# MCU.net
KiCad netlist of a schematic drawn in Altium Designer
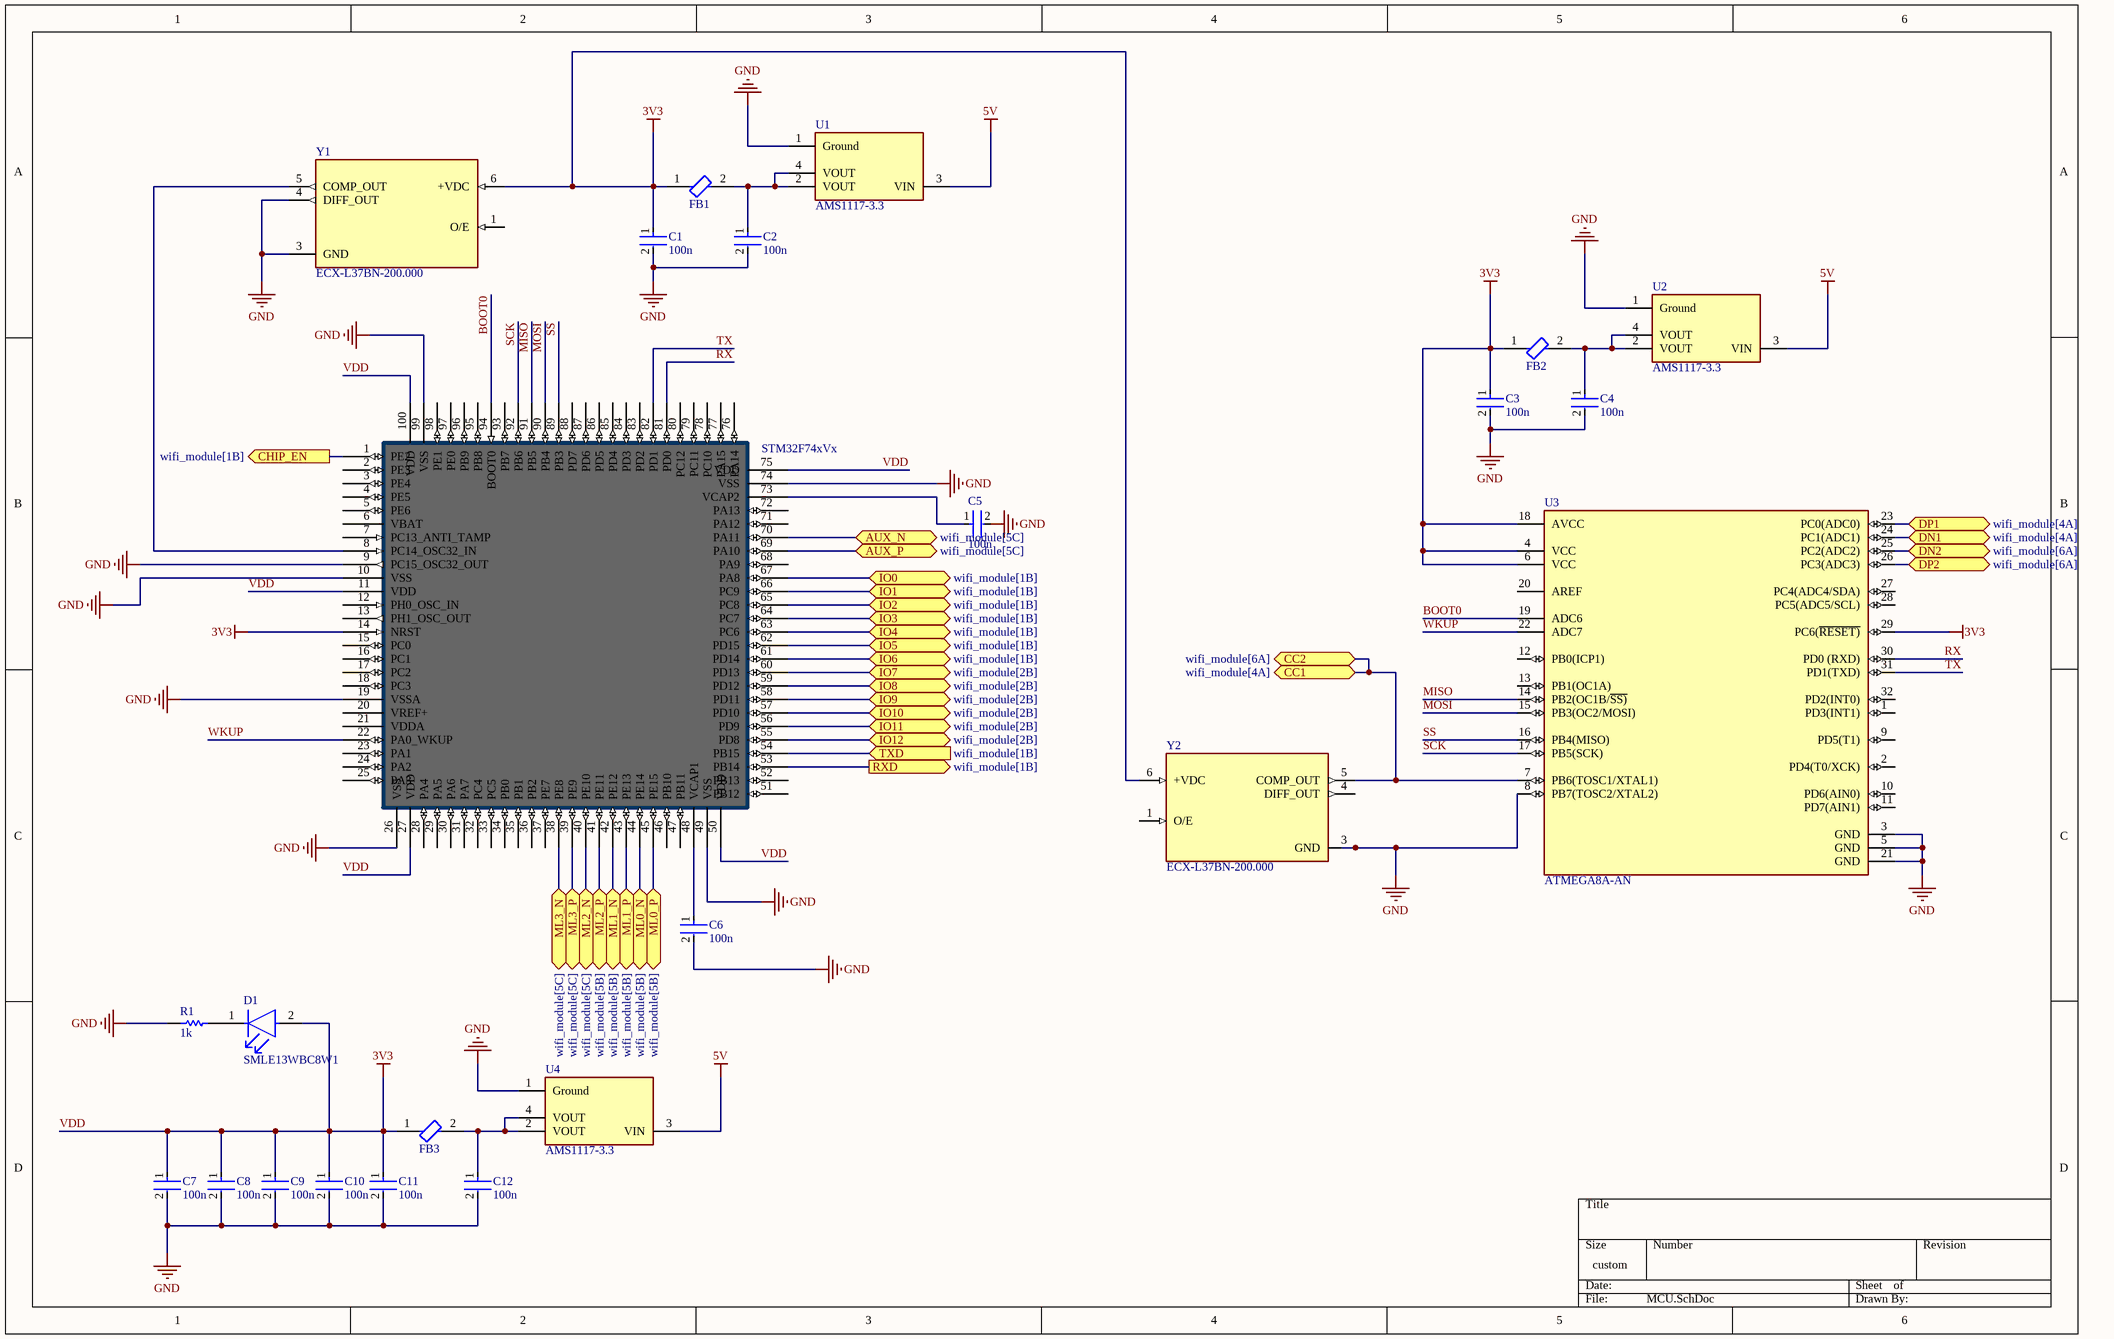
[diagram p0: MCU.SchDoc]

(export (version "E")
  (design (tool "Eeschema 10.0.6"))
  (components
    (comp (ref "C1")
      (value "100n")
      (footprint "FP-CL10-IPC_C")
      (description "Cap Ceramic 4.7uF 10V X5R ±10% Pad SMD 0603 +85°C T/R")
      (fields (field (name "TOLERANCE") "10%"))
      (libsource (lib "Altium Content Vault") (part "b4654b650e69147ec39a6b967a45e02"))
    )
    (comp (ref "C2")
      (value "100n")
      (footprint "FP-CL10-IPC_C")
      (description "Cap Ceramic 4.7uF 10V X5R ±10% Pad SMD 0603 +85°C T/R")
      (fields (field (name "TOLERANCE") "10%"))
      (libsource (lib "Altium Content Vault") (part "b4654b650e69147ec39a6b967a45e02"))
    )
    (comp (ref "C3")
      (value "100n")
      (footprint "FP-CL10-IPC_C")
      (description "Cap Ceramic 4.7uF 10V X5R ±10% Pad SMD 0603 +85°C T/R")
      (fields (field (name "TOLERANCE") "10%"))
      (libsource (lib "Altium Content Vault") (part "b4654b650e69147ec39a6b967a45e02"))
    )
    (comp (ref "C4")
      (value "100n")
      (footprint "FP-CL10-IPC_C")
      (description "Cap Ceramic 4.7uF 10V X5R ±10% Pad SMD 0603 +85°C T/R")
      (fields (field (name "TOLERANCE") "10%"))
      (libsource (lib "Altium Content Vault") (part "b4654b650e69147ec39a6b967a45e02"))
    )
    (comp (ref "C5")
      (value "100n")
      (footprint "FP-CL10-IPC_C")
      (description "Cap Ceramic 4.7uF 10V X5R ±10% Pad SMD 0603 +85°C T/R")
      (fields (field (name "TOLERANCE") "10%"))
      (libsource (lib "Altium Content Vault") (part "b4654b650e69147ec39a6b967a45e02"))
    )
    (comp (ref "C6")
      (value "100n")
      (footprint "FP-CL10-IPC_C")
      (description "Cap Ceramic 4.7uF 10V X5R ±10% Pad SMD 0603 +85°C T/R")
      (fields (field (name "TOLERANCE") "10%"))
      (libsource (lib "Altium Content Vault") (part "b4654b650e69147ec39a6b967a45e02"))
    )
    (comp (ref "C7")
      (value "100n")
      (footprint "FP-CL10-IPC_C")
      (description "Cap Ceramic 4.7uF 10V X5R ±10% Pad SMD 0603 +85°C T/R")
      (fields (field (name "TOLERANCE") "10%"))
      (libsource (lib "Altium Content Vault") (part "b4654b650e69147ec39a6b967a45e02"))
    )
    (comp (ref "C8")
      (value "100n")
      (footprint "FP-CL10-IPC_C")
      (description "Cap Ceramic 4.7uF 10V X5R ±10% Pad SMD 0603 +85°C T/R")
      (fields (field (name "TOLERANCE") "10%"))
      (libsource (lib "Altium Content Vault") (part "b4654b650e69147ec39a6b967a45e02"))
    )
    (comp (ref "C9")
      (value "100n")
      (footprint "FP-CL10-IPC_C")
      (description "Cap Ceramic 4.7uF 10V X5R ±10% Pad SMD 0603 +85°C T/R")
      (fields (field (name "TOLERANCE") "10%"))
      (libsource (lib "Altium Content Vault") (part "b4654b650e69147ec39a6b967a45e02"))
    )
    (comp (ref "C10")
      (value "100n")
      (footprint "FP-CL10-IPC_C")
      (description "Cap Ceramic 4.7uF 10V X5R ±10% Pad SMD 0603 +85°C T/R")
      (fields (field (name "TOLERANCE") "10%"))
      (libsource (lib "Altium Content Vault") (part "b4654b650e69147ec39a6b967a45e02"))
    )
    (comp (ref "C11")
      (value "100n")
      (footprint "FP-CL10-IPC_C")
      (description "Cap Ceramic 4.7uF 10V X5R ±10% Pad SMD 0603 +85°C T/R")
      (fields (field (name "TOLERANCE") "10%"))
      (libsource (lib "Altium Content Vault") (part "b4654b650e69147ec39a6b967a45e02"))
    )
    (comp (ref "C12")
      (value "100n")
      (footprint "FP-CL10-IPC_C")
      (description "Cap Ceramic 4.7uF 10V X5R ±10% Pad SMD 0603 +85°C T/R")
      (fields (field (name "TOLERANCE") "10%"))
      (libsource (lib "Altium Content Vault") (part "b4654b650e69147ec39a6b967a45e02"))
    )
    (comp (ref "D1")
      (value "SMLE13WBC8W1")
      (footprint "FP-SMLE13WBC8W1-MFG")
      (description "LED WHITE 0603 SMD")
      (fields
        (field (name "OCTOPART") "https://octopart.com/smle13wbc8w1-rohm-22224565")
        (field (name "MANUFACTURER") "Rohm")
      )
      (libsource (lib "Altium Content Vault") (part "8706943c75ba83719d021d2fdc84c58"))
    )
    (comp (ref "FB1")
      (value "BLM18KG121TN1D")
      (footprint "FP-BLM18-0_15-t0_6-d1_2-IPC_A")
      (description "FERRITE BEAD 120 OHM 0603 1LN")
      (fields (field (name "TOLERANCE") "25%"))
      (libsource (lib "Altium Content Vault") (part "5f30dd21d616792df468990f7003faa"))
    )
    (comp (ref "FB2")
      (value "BLM18KG121TN1D")
      (footprint "FP-BLM18-0_15-t0_6-d1_2-IPC_A")
      (description "FERRITE BEAD 120 OHM 0603 1LN")
      (fields (field (name "TOLERANCE") "25%"))
      (libsource (lib "Altium Content Vault") (part "5f30dd21d616792df468990f7003faa"))
    )
    (comp (ref "FB3")
      (value "BLM18KG121TN1D")
      (footprint "FP-BLM18-0_15-t0_6-d1_2-IPC_A")
      (description "FERRITE BEAD 120 OHM 0603 1LN")
      (fields (field (name "TOLERANCE") "25%"))
      (libsource (lib "Altium Content Vault") (part "5f30dd21d616792df468990f7003faa"))
    )
    (comp (ref "R1")
      (value "1k")
      (footprint "RESC2013X60X35ML10T20")
      (fields (field (name "TOLERANCE") "5%") (field (name "MANUFACTURER") "Yageo"))
      (libsource (lib "Altium Content Vault") (part "RES-2"))
    )
    (comp (ref "U0")
      (value "STM32F74xVx")
      (footprint "STMS:CQFP-STM32F74xVx")
      (description "STM32F74xVx LQFP100 pinout")
      (libsource (lib "STMs") (part "STM32F74xVx"))
    )
    (comp (ref "U1")
      (value "AMS1117-3.3")
      (footprint "FP-AMS1117-IPC_C")
      (description "LDO Voltage Regulators 1A, 3.3V")
      (fields
        (field (name "OCTOPART") "https://octopart.com/ams1117-3.3-advanced+monolithic+systems-25899300")
        (field (name "MANUFACTURER") "Advanced Monolithic Systems")
      )
      (libsource (lib "Altium Content Vault") (part "8bdbb5f8e77002000e30dd2845d0354"))
    )
    (comp (ref "U2")
      (value "AMS1117-3.3")
      (footprint "FP-AMS1117-IPC_C")
      (description "LDO Voltage Regulators 1A, 3.3V")
      (fields
        (field (name "OCTOPART") "https://octopart.com/ams1117-3.3-advanced+monolithic+systems-25899300")
        (field (name "MANUFACTURER") "Advanced Monolithic Systems")
      )
      (libsource (lib "Altium Content Vault") (part "8bdbb5f8e77002000e30dd2845d0354"))
    )
    (comp (ref "U3")
      (value "ATMEGA8A-AN")
      (footprint "FP-C04-074-PT-MFG")
      (description "ATMEGA8A-AN RISC Microcontroller, 8-Bit, FLASH, 16MHz, CMOS, PQFP32")
      (libsource (lib "Altium Content Vault") (part "c0b57bf7e3282e7022ba109d8523e59"))
    )
    (comp (ref "U4")
      (value "AMS1117-3.3")
      (footprint "FP-AMS1117-IPC_C")
      (description "LDO Voltage Regulators 1A, 3.3V")
      (fields
        (field (name "OCTOPART") "https://octopart.com/ams1117-3.3-advanced+monolithic+systems-25899300")
        (field (name "MANUFACTURER") "Advanced Monolithic Systems")
      )
      (libsource (lib "Altium Content Vault") (part "8bdbb5f8e77002000e30dd2845d0354"))
    )
    (comp (ref "Y1")
      (value "ECX-L37BN-200.000")
      (footprint "OSC_ECX-L37BN-200.000")
      (description "200 MHz XO (Standard) LVDS Oscillator 3.3V Enable/Disable 6-SMD, No Lead")
      (fields (field (name "MF") "ECS Inc."))
      (libsource (lib "ECX-L37BN-200.000") (part "ECX-L37BN-200.000"))
    )
    (comp (ref "Y2")
      (value "ECX-L37BN-200.000")
      (footprint "OSC_ECX-L37BN-200.000")
      (description "200 MHz XO (Standard) LVDS Oscillator 3.3V Enable/Disable 6-SMD, No Lead")
      (fields (field (name "MF") "ECS Inc."))
      (libsource (lib "") (part "ECX-L37BN-200.000_1"))
    )
  )
  (nets
    (net (code "1") (name "/AUX_N") (class "Default")
      (node (ref "U0") (pin "70") (pinfunction "PA11_70") (pintype "bidirectional"))
    )
    (net (code "2") (name "/AUX_P") (class "Default")
      (node (ref "U0") (pin "69") (pinfunction "PA10_69") (pintype "bidirectional"))
    )
    (net (code "3") (name "/BOOT0") (class "Default")
      (node (ref "U0") (pin "94") (pinfunction "BOOT0_94") (pintype "input"))
      (node (ref "U3") (pin "19") (pinfunction "ADC6_19") (pintype "passive"))
    )
    (net (code "4") (name "/CC1") (class "Default")
      (node (ref "U3") (pin "7") (pinfunction "PB6(TOSC1/XTAL1)_7") (pintype "bidirectional"))
      (node (ref "Y2") (pin "5") (pinfunction "COMP_OUT_5") (pintype "output"))
    )
    (net (code "5") (name "/CHIP_EN") (class "Default")
      (node (ref "U0") (pin "1") (pinfunction "PE2_1") (pintype "bidirectional"))
    )
    (net (code "6") (name "/DN1") (class "Default")
      (node (ref "U3") (pin "24") (pinfunction "PC1(ADC1)_24") (pintype "bidirectional"))
    )
    (net (code "7") (name "/DN2") (class "Default")
      (node (ref "U3") (pin "25") (pinfunction "PC2(ADC2)_25") (pintype "bidirectional"))
    )
    (net (code "8") (name "/DP1") (class "Default")
      (node (ref "U3") (pin "23") (pinfunction "PC0(ADC0)_23") (pintype "bidirectional"))
    )
    (net (code "9") (name "/DP2") (class "Default")
      (node (ref "U3") (pin "26") (pinfunction "PC3(ADC3)_26") (pintype "bidirectional"))
    )
    (net (code "10") (name "/IO0") (class "Default")
      (node (ref "U0") (pin "67") (pinfunction "PA8_67") (pintype "bidirectional"))
    )
    (net (code "11") (name "/IO1") (class "Default")
      (node (ref "U0") (pin "66") (pinfunction "PC9_66") (pintype "bidirectional"))
    )
    (net (code "12") (name "/IO2") (class "Default")
      (node (ref "U0") (pin "65") (pinfunction "PC8_65") (pintype "bidirectional"))
    )
    (net (code "13") (name "/IO3") (class "Default")
      (node (ref "U0") (pin "64") (pinfunction "PC7_64") (pintype "bidirectional"))
    )
    (net (code "14") (name "/IO4") (class "Default")
      (node (ref "U0") (pin "63") (pinfunction "PC6_63") (pintype "bidirectional"))
    )
    (net (code "15") (name "/IO5") (class "Default")
      (node (ref "U0") (pin "62") (pinfunction "PD15_62") (pintype "bidirectional"))
    )
    (net (code "16") (name "/IO6") (class "Default")
      (node (ref "U0") (pin "61") (pinfunction "PD14_61") (pintype "bidirectional"))
    )
    (net (code "17") (name "/IO7") (class "Default")
      (node (ref "U0") (pin "60") (pinfunction "PD13_60") (pintype "bidirectional"))
    )
    (net (code "18") (name "/IO8") (class "Default")
      (node (ref "U0") (pin "59") (pinfunction "PD12_59") (pintype "bidirectional"))
    )
    (net (code "19") (name "/IO9") (class "Default")
      (node (ref "U0") (pin "58") (pinfunction "PD11_58") (pintype "bidirectional"))
    )
    (net (code "20") (name "/IO10") (class "Default")
      (node (ref "U0") (pin "57") (pinfunction "PD10_57") (pintype "bidirectional"))
    )
    (net (code "21") (name "/IO11") (class "Default")
      (node (ref "U0") (pin "56") (pinfunction "PD9_56") (pintype "bidirectional"))
    )
    (net (code "22") (name "/IO12") (class "Default")
      (node (ref "U0") (pin "55") (pinfunction "PD8_55") (pintype "bidirectional"))
    )
    (net (code "23") (name "/MISO") (class "Default")
      (node (ref "U0") (pin "91") (pinfunction "PB5_91") (pintype "bidirectional"))
      (node (ref "U3") (pin "14") (pinfunction "PB2(OC1B/~{SS)}_14") (pintype "bidirectional"))
    )
    (net (code "24") (name "/ML0_N") (class "Default")
      (node (ref "U0") (pin "44") (pinfunction "PE14_44") (pintype "bidirectional"))
    )
    (net (code "25") (name "/ML0_P") (class "Default")
      (node (ref "U0") (pin "45") (pinfunction "PE15_45") (pintype "bidirectional"))
    )
    (net (code "26") (name "/ML1_N") (class "Default")
      (node (ref "U0") (pin "42") (pinfunction "PE12_42") (pintype "bidirectional"))
    )
    (net (code "27") (name "/ML1_P") (class "Default")
      (node (ref "U0") (pin "43") (pinfunction "PE13_43") (pintype "bidirectional"))
    )
    (net (code "28") (name "/ML2_N") (class "Default")
      (node (ref "U0") (pin "40") (pinfunction "PE10_40") (pintype "bidirectional"))
    )
    (net (code "29") (name "/ML2_P") (class "Default")
      (node (ref "U0") (pin "41") (pinfunction "PE11_41") (pintype "bidirectional"))
    )
    (net (code "30") (name "/ML3_N") (class "Default")
      (node (ref "U0") (pin "38") (pinfunction "PE8_38") (pintype "bidirectional"))
    )
    (net (code "31") (name "/ML3_P") (class "Default")
      (node (ref "U0") (pin "39") (pinfunction "PE9_39") (pintype "bidirectional"))
    )
    (net (code "32") (name "/MOSI") (class "Default")
      (node (ref "U0") (pin "90") (pinfunction "PB4_90") (pintype "bidirectional"))
      (node (ref "U3") (pin "15") (pinfunction "PB3(OC2/MOSI)_15") (pintype "bidirectional"))
    )
    (net (code "33") (name "/RX") (class "Default")
      (node (ref "U0") (pin "81") (pinfunction "PD0_81") (pintype "bidirectional"))
      (node (ref "U3") (pin "30") (pinfunction "PD0_(RXD)_30") (pintype "bidirectional"))
    )
    (net (code "34") (name "/RXD") (class "Default")
      (node (ref "U0") (pin "53") (pinfunction "PB14_53") (pintype "bidirectional"))
    )
    (net (code "35") (name "/SCK") (class "Default")
      (node (ref "U0") (pin "92") (pinfunction "PB6_92") (pintype "bidirectional"))
      (node (ref "U3") (pin "17") (pinfunction "PB5(SCK)_17") (pintype "bidirectional"))
    )
    (net (code "36") (name "/SS") (class "Default")
      (node (ref "U0") (pin "89") (pinfunction "PB3_89") (pintype "bidirectional"))
      (node (ref "U3") (pin "16") (pinfunction "PB4(MISO)_16") (pintype "bidirectional"))
    )
    (net (code "37") (name "/TX") (class "Default")
      (node (ref "U0") (pin "82") (pinfunction "PD1_82") (pintype "bidirectional"))
      (node (ref "U3") (pin "31") (pinfunction "PD1(TXD)_31") (pintype "bidirectional"))
    )
    (net (code "38") (name "/TXD") (class "Default")
      (node (ref "U0") (pin "54") (pinfunction "PB15_54") (pintype "bidirectional"))
    )
    (net (code "39") (name "/WKUP") (class "Default")
      (node (ref "U0") (pin "22") (pinfunction "PA0_WKUP_22") (pintype "bidirectional"))
      (node (ref "U3") (pin "22") (pinfunction "ADC7_22") (pintype "passive"))
    )
    (net (code "40") (name "3V3") (class "Default")
      (node (ref "C1") (pin "1") (pinfunction "1_1") (pintype "passive"))
      (node (ref "C10") (pin "1") (pinfunction "1_1") (pintype "passive"))
      (node (ref "C11") (pin "1") (pinfunction "1_1") (pintype "passive"))
      (node (ref "C3") (pin "1") (pinfunction "1_1") (pintype "passive"))
      (node (ref "C7") (pin "1") (pinfunction "1_1") (pintype "passive"))
      (node (ref "C8") (pin "1") (pinfunction "1_1") (pintype "passive"))
      (node (ref "C9") (pin "1") (pinfunction "1_1") (pintype "passive"))
      (node (ref "D1") (pin "2") (pinfunction "A_2") (pintype "passive"))
      (node (ref "FB1") (pin "1") (pinfunction "1_1") (pintype "passive"))
      (node (ref "FB2") (pin "1") (pinfunction "1_1") (pintype "passive"))
      (node (ref "FB3") (pin "1") (pinfunction "1_1") (pintype "passive"))
      (node (ref "U0") (pin "100") (pinfunction "VDD_100") (pintype "power_in"))
      (node (ref "U0") (pin "11") (pinfunction "VDD_11") (pintype "power_in"))
      (node (ref "U0") (pin "14") (pinfunction "NRST_14") (pintype "input"))
      (node (ref "U0") (pin "27") (pinfunction "VDD_27") (pintype "power_in"))
      (node (ref "U0") (pin "50") (pinfunction "VDD_50") (pintype "power_in"))
      (node (ref "U0") (pin "75") (pinfunction "VDD_75") (pintype "power_in"))
      (node (ref "U3") (pin "18") (pinfunction "AVCC_18") (pintype "power_in"))
      (node (ref "U3") (pin "29") (pinfunction "PC6(~{RESET)}_29") (pintype "bidirectional"))
      (node (ref "U3") (pin "4") (pinfunction "VCC_4") (pintype "power_in"))
      (node (ref "U3") (pin "6") (pinfunction "VCC_6") (pintype "power_in"))
      (node (ref "Y1") (pin "6") (pinfunction "+VDC_6") (pintype "input"))
      (node (ref "Y2") (pin "6") (pinfunction "+VDC_6") (pintype "input"))
    )
    (net (code "41") (name "5V") (class "Default")
      (node (ref "U1") (pin "3") (pinfunction "VIN_3") (pintype "power_in"))
      (node (ref "U2") (pin "3") (pinfunction "VIN_3") (pintype "power_in"))
      (node (ref "U4") (pin "3") (pinfunction "VIN_3") (pintype "power_in"))
    )
    (net (code "42") (name "GND") (class "Default")
      (node (ref "C1") (pin "2") (pinfunction "2_2") (pintype "passive"))
      (node (ref "C10") (pin "2") (pinfunction "2_2") (pintype "passive"))
      (node (ref "C11") (pin "2") (pinfunction "2_2") (pintype "passive"))
      (node (ref "C12") (pin "2") (pinfunction "2_2") (pintype "passive"))
      (node (ref "C2") (pin "2") (pinfunction "2_2") (pintype "passive"))
      (node (ref "C3") (pin "2") (pinfunction "2_2") (pintype "passive"))
      (node (ref "C4") (pin "2") (pinfunction "2_2") (pintype "passive"))
      (node (ref "C5") (pin "2") (pinfunction "2_2") (pintype "passive"))
      (node (ref "C6") (pin "2") (pinfunction "2_2") (pintype "passive"))
      (node (ref "C7") (pin "2") (pinfunction "2_2") (pintype "passive"))
      (node (ref "C8") (pin "2") (pinfunction "2_2") (pintype "passive"))
      (node (ref "C9") (pin "2") (pinfunction "2_2") (pintype "passive"))
      (node (ref "R1") (pin "1") (pinfunction "1_1") (pintype "passive"))
      (node (ref "U0") (pin "10") (pinfunction "VSS_10") (pintype "power_in"))
      (node (ref "U0") (pin "19") (pinfunction "VSSA_19") (pintype "power_in"))
      (node (ref "U0") (pin "26") (pinfunction "VSS_26") (pintype "power_in"))
      (node (ref "U0") (pin "49") (pinfunction "VSS_49") (pintype "power_in"))
      (node (ref "U0") (pin "74") (pinfunction "VSS_74") (pintype "power_in"))
      (node (ref "U0") (pin "9") (pinfunction "PC15_OSC32_OUT_9") (pintype "output"))
      (node (ref "U0") (pin "99") (pinfunction "VSS_99") (pintype "power_in"))
      (node (ref "U1") (pin "1") (pinfunction "Ground_1") (pintype "power_in"))
      (node (ref "U2") (pin "1") (pinfunction "Ground_1") (pintype "power_in"))
      (node (ref "U3") (pin "21") (pinfunction "GND_21") (pintype "power_in"))
      (node (ref "U3") (pin "3") (pinfunction "GND_3") (pintype "power_in"))
      (node (ref "U3") (pin "5") (pinfunction "GND_5") (pintype "power_in"))
      (node (ref "U3") (pin "8") (pinfunction "PB7(TOSC2/XTAL2)_8") (pintype "bidirectional"))
      (node (ref "U4") (pin "1") (pinfunction "Ground_1") (pintype "power_in"))
      (node (ref "Y1") (pin "3") (pinfunction "GND_3") (pintype "power_in"))
      (node (ref "Y1") (pin "4") (pinfunction "DIFF_OUT_4") (pintype "output"))
      (node (ref "Y2") (pin "3") (pinfunction "GND_3") (pintype "power_in"))
    )
    (net (code "43") (name "Net-(C2-Pad1)") (class "Default")
      (node (ref "C2") (pin "1") (pinfunction "1_1") (pintype "passive"))
      (node (ref "FB1") (pin "2") (pinfunction "2_2") (pintype "passive"))
      (node (ref "U1") (pin "2") (pinfunction "VOUT_2") (pintype "passive"))
      (node (ref "U1") (pin "4") (pinfunction "VOUT_4") (pintype "passive"))
    )
    (net (code "44") (name "Net-(C4-Pad1)") (class "Default")
      (node (ref "C4") (pin "1") (pinfunction "1_1") (pintype "passive"))
      (node (ref "FB2") (pin "2") (pinfunction "2_2") (pintype "passive"))
      (node (ref "U2") (pin "2") (pinfunction "VOUT_2") (pintype "passive"))
      (node (ref "U2") (pin "4") (pinfunction "VOUT_4") (pintype "passive"))
    )
    (net (code "45") (name "Net-(C12-Pad1)") (class "Default")
      (node (ref "C12") (pin "1") (pinfunction "1_1") (pintype "passive"))
      (node (ref "FB3") (pin "2") (pinfunction "2_2") (pintype "passive"))
      (node (ref "U4") (pin "2") (pinfunction "VOUT_2") (pintype "passive"))
      (node (ref "U4") (pin "4") (pinfunction "VOUT_4") (pintype "passive"))
    )
    (net (code "46") (name "Net-(D1-C)") (class "Default")
      (node (ref "D1") (pin "1") (pinfunction "C_1") (pintype "passive"))
      (node (ref "R1") (pin "2") (pinfunction "2_2") (pintype "passive"))
    )
    (net (code "47") (name "Net-(U0-PC14_OSC32_IN)") (class "Default")
      (node (ref "U0") (pin "8") (pinfunction "PC14_OSC32_IN_8") (pintype "input"))
      (node (ref "Y1") (pin "5") (pinfunction "COMP_OUT_5") (pintype "output"))
    )
    (net (code "48") (name "Net-(U0-VCAP1)") (class "Default")
      (node (ref "C6") (pin "1") (pinfunction "1_1") (pintype "passive"))
      (node (ref "U0") (pin "48") (pinfunction "VCAP1_48") (pintype "power_in"))
    )
    (net (code "49") (name "Net-(U0-VCAP2)") (class "Default")
      (node (ref "C5") (pin "1") (pinfunction "1_1") (pintype "passive"))
      (node (ref "U0") (pin "73") (pinfunction "VCAP2_73") (pintype "power_in"))
    )
    (net (code "50") (name "unconnected-(U0-PA1-Pad23)") (class "Default")
      (node (ref "U0") (pin "23") (pinfunction "PA1_23") (pintype "bidirectional"))
    )
    (net (code "51") (name "unconnected-(U0-PA2-Pad24)") (class "Default")
      (node (ref "U0") (pin "24") (pinfunction "PA2_24") (pintype "bidirectional"))
    )
    (net (code "52") (name "unconnected-(U0-PA3-Pad25)") (class "Default")
      (node (ref "U0") (pin "25") (pinfunction "PA3_25") (pintype "bidirectional"))
    )
    (net (code "53") (name "unconnected-(U0-PA4-Pad28)") (class "Default")
      (node (ref "U0") (pin "28") (pinfunction "PA4_28") (pintype "bidirectional"))
    )
    (net (code "54") (name "unconnected-(U0-PA5-Pad29)") (class "Default")
      (node (ref "U0") (pin "29") (pinfunction "PA5_29") (pintype "bidirectional"))
    )
    (net (code "55") (name "unconnected-(U0-PA6-Pad30)") (class "Default")
      (node (ref "U0") (pin "30") (pinfunction "PA6_30") (pintype "bidirectional"))
    )
    (net (code "56") (name "unconnected-(U0-PA7-Pad31)") (class "Default")
      (node (ref "U0") (pin "31") (pinfunction "PA7_31") (pintype "bidirectional"))
    )
    (net (code "57") (name "unconnected-(U0-PA9-Pad68)") (class "Default")
      (node (ref "U0") (pin "68") (pinfunction "PA9_68") (pintype "bidirectional"))
    )
    (net (code "58") (name "unconnected-(U0-PA12-Pad71)") (class "Default")
      (node (ref "U0") (pin "71") (pinfunction "PA12_71") (pintype "bidirectional"))
    )
    (net (code "59") (name "unconnected-(U0-PA13-Pad72)") (class "Default")
      (node (ref "U0") (pin "72") (pinfunction "PA13_72") (pintype "bidirectional"))
    )
    (net (code "60") (name "unconnected-(U0-PA14-Pad76)") (class "Default")
      (node (ref "U0") (pin "76") (pinfunction "PA14_76") (pintype "bidirectional"))
    )
    (net (code "61") (name "unconnected-(U0-PA15-Pad77)") (class "Default")
      (node (ref "U0") (pin "77") (pinfunction "PA15_77") (pintype "bidirectional"))
    )
    (net (code "62") (name "unconnected-(U0-PB0-Pad34)") (class "Default")
      (node (ref "U0") (pin "34") (pinfunction "PB0_34") (pintype "bidirectional"))
    )
    (net (code "63") (name "unconnected-(U0-PB1-Pad35)") (class "Default")
      (node (ref "U0") (pin "35") (pinfunction "PB1_35") (pintype "bidirectional"))
    )
    (net (code "64") (name "unconnected-(U0-PB2-Pad36)") (class "Default")
      (node (ref "U0") (pin "36") (pinfunction "PB2_36") (pintype "bidirectional"))
    )
    (net (code "65") (name "unconnected-(U0-PB7-Pad93)") (class "Default")
      (node (ref "U0") (pin "93") (pinfunction "PB7_93") (pintype "bidirectional"))
    )
    (net (code "66") (name "unconnected-(U0-PB8-Pad95)") (class "Default")
      (node (ref "U0") (pin "95") (pinfunction "PB8_95") (pintype "bidirectional"))
    )
    (net (code "67") (name "unconnected-(U0-PB9-Pad96)") (class "Default")
      (node (ref "U0") (pin "96") (pinfunction "PB9_96") (pintype "bidirectional"))
    )
    (net (code "68") (name "unconnected-(U0-PB10-Pad46)") (class "Default")
      (node (ref "U0") (pin "46") (pinfunction "PB10_46") (pintype "bidirectional"))
    )
    (net (code "69") (name "unconnected-(U0-PB11-Pad47)") (class "Default")
      (node (ref "U0") (pin "47") (pinfunction "PB11_47") (pintype "bidirectional"))
    )
    (net (code "70") (name "unconnected-(U0-PB12-Pad51)") (class "Default")
      (node (ref "U0") (pin "51") (pinfunction "PB12_51") (pintype "bidirectional"))
    )
    (net (code "71") (name "unconnected-(U0-PB13-Pad52)") (class "Default")
      (node (ref "U0") (pin "52") (pinfunction "PB13_52") (pintype "bidirectional"))
    )
    (net (code "72") (name "unconnected-(U0-PC0-Pad15)") (class "Default")
      (node (ref "U0") (pin "15") (pinfunction "PC0_15") (pintype "bidirectional"))
    )
    (net (code "73") (name "unconnected-(U0-PC1-Pad16)") (class "Default")
      (node (ref "U0") (pin "16") (pinfunction "PC1_16") (pintype "bidirectional"))
    )
    (net (code "74") (name "unconnected-(U0-PC2-Pad17)") (class "Default")
      (node (ref "U0") (pin "17") (pinfunction "PC2_17") (pintype "bidirectional"))
    )
    (net (code "75") (name "unconnected-(U0-PC3-Pad18)") (class "Default")
      (node (ref "U0") (pin "18") (pinfunction "PC3_18") (pintype "bidirectional"))
    )
    (net (code "76") (name "unconnected-(U0-PC4-Pad32)") (class "Default")
      (node (ref "U0") (pin "32") (pinfunction "PC4_32") (pintype "bidirectional"))
    )
    (net (code "77") (name "unconnected-(U0-PC5-Pad33)") (class "Default")
      (node (ref "U0") (pin "33") (pinfunction "PC5_33") (pintype "bidirectional"))
    )
    (net (code "78") (name "unconnected-(U0-PC10-Pad78)") (class "Default")
      (node (ref "U0") (pin "78") (pinfunction "PC10_78") (pintype "bidirectional"))
    )
    (net (code "79") (name "unconnected-(U0-PC11-Pad79)") (class "Default")
      (node (ref "U0") (pin "79") (pinfunction "PC11_79") (pintype "bidirectional"))
    )
    (net (code "80") (name "unconnected-(U0-PC12-Pad80)") (class "Default")
      (node (ref "U0") (pin "80") (pinfunction "PC12_80") (pintype "bidirectional"))
    )
    (net (code "81") (name "unconnected-(U0-PC13_ANTI_TAMP-Pad7)") (class "Default")
      (node (ref "U0") (pin "7") (pinfunction "PC13_ANTI_TAMP_7") (pintype "input"))
    )
    (net (code "82") (name "unconnected-(U0-PD2-Pad83)") (class "Default")
      (node (ref "U0") (pin "83") (pinfunction "PD2_83") (pintype "bidirectional"))
    )
    (net (code "83") (name "unconnected-(U0-PD3-Pad84)") (class "Default")
      (node (ref "U0") (pin "84") (pinfunction "PD3_84") (pintype "bidirectional"))
    )
    (net (code "84") (name "unconnected-(U0-PD4-Pad85)") (class "Default")
      (node (ref "U0") (pin "85") (pinfunction "PD4_85") (pintype "bidirectional"))
    )
    (net (code "85") (name "unconnected-(U0-PD5-Pad86)") (class "Default")
      (node (ref "U0") (pin "86") (pinfunction "PD5_86") (pintype "bidirectional"))
    )
    (net (code "86") (name "unconnected-(U0-PD6-Pad87)") (class "Default")
      (node (ref "U0") (pin "87") (pinfunction "PD6_87") (pintype "bidirectional"))
    )
    (net (code "87") (name "unconnected-(U0-PD7-Pad88)") (class "Default")
      (node (ref "U0") (pin "88") (pinfunction "PD7_88") (pintype "bidirectional"))
    )
    (net (code "88") (name "unconnected-(U0-PE0-Pad97)") (class "Default")
      (node (ref "U0") (pin "97") (pinfunction "PE0_97") (pintype "bidirectional"))
    )
    (net (code "89") (name "unconnected-(U0-PE1-Pad98)") (class "Default")
      (node (ref "U0") (pin "98") (pinfunction "PE1_98") (pintype "bidirectional"))
    )
    (net (code "90") (name "unconnected-(U0-PE3-Pad2)") (class "Default")
      (node (ref "U0") (pin "2") (pinfunction "PE3_2") (pintype "bidirectional"))
    )
    (net (code "91") (name "unconnected-(U0-PE4-Pad3)") (class "Default")
      (node (ref "U0") (pin "3") (pinfunction "PE4_3") (pintype "bidirectional"))
    )
    (net (code "92") (name "unconnected-(U0-PE5-Pad4)") (class "Default")
      (node (ref "U0") (pin "4") (pinfunction "PE5_4") (pintype "bidirectional"))
    )
    (net (code "93") (name "unconnected-(U0-PE6-Pad5)") (class "Default")
      (node (ref "U0") (pin "5") (pinfunction "PE6_5") (pintype "bidirectional"))
    )
    (net (code "94") (name "unconnected-(U0-PE7-Pad37)") (class "Default")
      (node (ref "U0") (pin "37") (pinfunction "PE7_37") (pintype "bidirectional"))
    )
    (net (code "95") (name "unconnected-(U0-PH0_OSC_IN-Pad12)") (class "Default")
      (node (ref "U0") (pin "12") (pinfunction "PH0_OSC_IN_12") (pintype "input"))
    )
    (net (code "96") (name "unconnected-(U0-PH1_OSC_OUT-Pad13)") (class "Default")
      (node (ref "U0") (pin "13") (pinfunction "PH1_OSC_OUT_13") (pintype "output"))
    )
    (net (code "97") (name "unconnected-(U0-VBAT-Pad6)") (class "Default")
      (node (ref "U0") (pin "6") (pinfunction "VBAT_6") (pintype "power_in"))
    )
    (net (code "98") (name "unconnected-(U0-VDDA-Pad21)") (class "Default")
      (node (ref "U0") (pin "21") (pinfunction "VDDA_21") (pintype "power_in"))
    )
    (net (code "99") (name "unconnected-(U0-VREF+-Pad20)") (class "Default")
      (node (ref "U0") (pin "20") (pinfunction "VREF+_20") (pintype "power_in"))
    )
    (net (code "100") (name "unconnected-(U3-AREF-Pad20)") (class "Default")
      (node (ref "U3") (pin "20") (pinfunction "AREF_20") (pintype "passive"))
    )
    (net (code "101") (name "unconnected-(U3-PB0(ICP1)-Pad12)") (class "Default")
      (node (ref "U3") (pin "12") (pinfunction "PB0(ICP1)_12") (pintype "bidirectional"))
    )
    (net (code "102") (name "unconnected-(U3-PB1(OC1A)-Pad13)") (class "Default")
      (node (ref "U3") (pin "13") (pinfunction "PB1(OC1A)_13") (pintype "bidirectional"))
    )
    (net (code "103") (name "unconnected-(U3-PC4(ADC4{slash}SDA)-Pad27)") (class "Default")
      (node (ref "U3") (pin "27") (pinfunction "PC4(ADC4/SDA)_27") (pintype "bidirectional"))
    )
    (net (code "104") (name "unconnected-(U3-PC5(ADC5{slash}SCL)-Pad28)") (class "Default")
      (node (ref "U3") (pin "28") (pinfunction "PC5(ADC5/SCL)_28") (pintype "bidirectional"))
    )
    (net (code "105") (name "unconnected-(U3-PD2(INT0)-Pad32)") (class "Default")
      (node (ref "U3") (pin "32") (pinfunction "PD2(INT0)_32") (pintype "bidirectional"))
    )
    (net (code "106") (name "unconnected-(U3-PD3(INT1)-Pad1)") (class "Default")
      (node (ref "U3") (pin "1") (pinfunction "PD3(INT1)_1") (pintype "bidirectional"))
    )
    (net (code "107") (name "unconnected-(U3-PD4(T0{slash}XCK)-Pad2)") (class "Default")
      (node (ref "U3") (pin "2") (pinfunction "PD4(T0/XCK)_2") (pintype "bidirectional"))
    )
    (net (code "108") (name "unconnected-(U3-PD5(T1)-Pad9)") (class "Default")
      (node (ref "U3") (pin "9") (pinfunction "PD5(T1)_9") (pintype "bidirectional"))
    )
    (net (code "109") (name "unconnected-(U3-PD6(AIN0)-Pad10)") (class "Default")
      (node (ref "U3") (pin "10") (pinfunction "PD6(AIN0)_10") (pintype "bidirectional"))
    )
    (net (code "110") (name "unconnected-(U3-PD7(AIN1)-Pad11)") (class "Default")
      (node (ref "U3") (pin "11") (pinfunction "PD7(AIN1)_11") (pintype "bidirectional"))
    )
    (net (code "111") (name "unconnected-(Y1-O{slash}E-Pad1)") (class "Default")
      (node (ref "Y1") (pin "1") (pinfunction "O/E_1") (pintype "input"))
    )
    (net (code "112") (name "unconnected-(Y2-DIFF_OUT-Pad4)") (class "Default")
      (node (ref "Y2") (pin "4") (pinfunction "DIFF_OUT_4") (pintype "output"))
    )
    (net (code "113") (name "unconnected-(Y2-O{slash}E-Pad1)") (class "Default")
      (node (ref "Y2") (pin "1") (pinfunction "O/E_1") (pintype "input"))
    )
  )
)
